# prom.net
KiCad netlist of a schematic drawn in Altium Designer
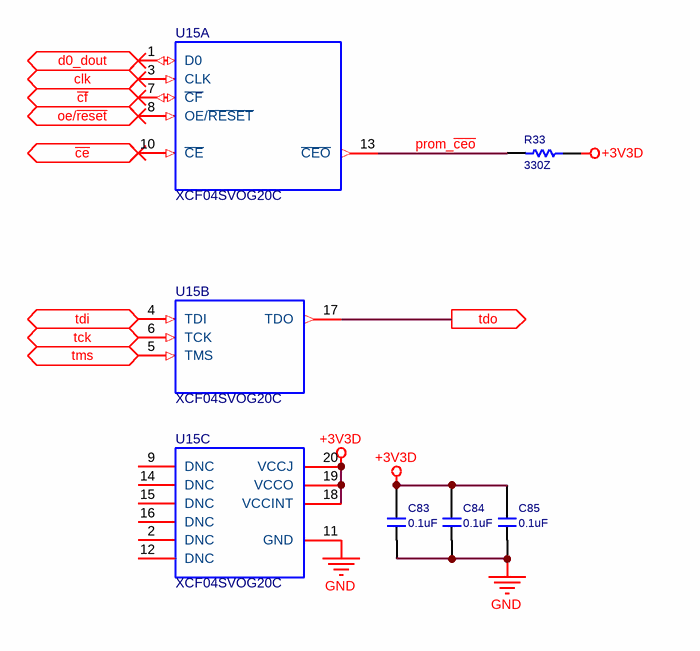
[diagram p0: prom.SchDoc]

(export (version "E")
  (design (tool "Eeschema 10.0.6"))
  (components
    (comp (ref "C83")
      (value "0.1uF")
      (footprint "C0603")
      (description "CAP-CER, 2, 0.1uF, 10%, 50V, 0603, X7R")
      (fields
        (field (name "MANUFACTURER") "AVX Corporation")
        (field (name "MANUFACTURER PART NUMBER") "06035C104KAT2A")
      )
      (libsource (lib "stdlib") (part "CAP/06035C104KAT2A"))
    )
    (comp (ref "C84")
      (value "0.1uF")
      (footprint "C0603")
      (description "CAP-CER, 2, 0.1uF, 10%, 50V, 0603, X7R")
      (fields
        (field (name "MANUFACTURER") "AVX Corporation")
        (field (name "MANUFACTURER PART NUMBER") "06035C104KAT2A")
      )
      (libsource (lib "stdlib") (part "CAP/06035C104KAT2A"))
    )
    (comp (ref "C85")
      (value "0.1uF")
      (footprint "C0603")
      (description "CAP-CER, 2, 0.1uF, 10%, 50V, 0603, X7R")
      (fields
        (field (name "MANUFACTURER") "AVX Corporation")
        (field (name "MANUFACTURER PART NUMBER") "06035C104KAT2A")
      )
      (libsource (lib "stdlib") (part "CAP/06035C104KAT2A"))
    )
    (comp (ref "R33")
      (value "330Z")
      (footprint "R0603")
      (description "RES0, SMD,  330Z, 1.0%, 1/10W, 0603")
      (fields
        (field (name "MANUFACTURER") "Rohm Semiconductor")
        (field (name "MANUFACTURER PART NUMBER") "MCR03ERTF3300")
      )
      (libsource (lib "stdlib") (part "CRCW0603330RFKEA"))
    )
    (comp (ref "U15")
      (value "XCF04SVOG20C")
      (footprint "R-PDSO-G20")
      (description "PROM, 4M GATE, Platform Flash")
      (fields (field (name "MANUFACTURER") "Xilinx Inc."))
      (libsource (lib "stdlib") (part "XCF04SVOG20C TSSOP-20"))
    )
  )
  (nets
    (net (code "1") (name "+3V3D") (class "Default")
      (node (ref "C83") (pin "2") (pinfunction "2_2") (pintype "passive"))
      (node (ref "C84") (pin "2") (pinfunction "2_2") (pintype "passive"))
      (node (ref "C85") (pin "2") (pinfunction "2_2") (pintype "passive"))
      (node (ref "R33") (pin "1") (pinfunction "1_1") (pintype "passive"))
      (node (ref "U15") (pin "18") (pinfunction "VCCINT_18") (pintype "power_in"))
      (node (ref "U15") (pin "19") (pinfunction "VCCO_19") (pintype "power_in"))
      (node (ref "U15") (pin "20") (pinfunction "VCCJ_20") (pintype "power_in"))
    )
    (net (code "2") (name "/clk") (class "Default")
      (node (ref "U15") (pin "3") (pinfunction "CLK_3") (pintype "input+no_connect"))
    )
    (net (code "3") (name "/d0_dout") (class "Default")
      (node (ref "U15") (pin "1") (pinfunction "D0_1") (pintype "bidirectional+no_connect"))
    )
    (net (code "4") (name "/oe{slash}~{reset}") (class "Default")
      (node (ref "U15") (pin "8") (pinfunction "OE/~{RESET}_8") (pintype "input+no_connect"))
    )
    (net (code "5") (name "/prom_~{ceo}") (class "Default")
      (node (ref "R33") (pin "2") (pinfunction "2_2") (pintype "passive"))
      (node (ref "U15") (pin "13") (pinfunction "~{CEO}_13") (pintype "output"))
    )
    (net (code "6") (name "/tck") (class "Default")
      (node (ref "U15") (pin "6") (pinfunction "TCK_6") (pintype "input"))
    )
    (net (code "7") (name "/tdi") (class "Default")
      (node (ref "U15") (pin "4") (pinfunction "TDI_4") (pintype "input"))
    )
    (net (code "8") (name "/tdo") (class "Default")
      (node (ref "U15") (pin "17") (pinfunction "TDO_17") (pintype "output"))
    )
    (net (code "9") (name "/tms") (class "Default")
      (node (ref "U15") (pin "5") (pinfunction "TMS_5") (pintype "input"))
    )
    (net (code "10") (name "/~{ce}") (class "Default")
      (node (ref "U15") (pin "10") (pinfunction "~{CE}_10") (pintype "input+no_connect"))
    )
    (net (code "11") (name "/~{cf}") (class "Default")
      (node (ref "U15") (pin "7") (pinfunction "~{CF}_7") (pintype "bidirectional+no_connect"))
    )
    (net (code "12") (name "GND") (class "Default")
      (node (ref "C83") (pin "1") (pinfunction "5_1") (pintype "passive"))
      (node (ref "C84") (pin "1") (pinfunction "5_1") (pintype "passive"))
      (node (ref "C85") (pin "1") (pinfunction "5_1") (pintype "passive"))
      (node (ref "U15") (pin "11") (pinfunction "GND_11") (pintype "power_in"))
    )
    (net (code "13") (name "unconnected-(U15C-DNC-Pad2)") (class "Default")
      (node (ref "U15") (pin "2") (pinfunction "DNC_2") (pintype "passive"))
    )
    (net (code "14") (name "unconnected-(U15C-DNC-Pad9)") (class "Default")
      (node (ref "U15") (pin "9") (pinfunction "DNC_9") (pintype "passive"))
    )
    (net (code "15") (name "unconnected-(U15C-DNC-Pad12)") (class "Default")
      (node (ref "U15") (pin "12") (pinfunction "DNC_12") (pintype "passive"))
    )
    (net (code "16") (name "unconnected-(U15C-DNC-Pad14)") (class "Default")
      (node (ref "U15") (pin "14") (pinfunction "DNC_14") (pintype "passive"))
    )
    (net (code "17") (name "unconnected-(U15C-DNC-Pad15)") (class "Default")
      (node (ref "U15") (pin "15") (pinfunction "DNC_15") (pintype "passive"))
    )
    (net (code "18") (name "unconnected-(U15C-DNC-Pad16)") (class "Default")
      (node (ref "U15") (pin "16") (pinfunction "DNC_16") (pintype "passive"))
    )
  )
)
